# 05_LMS7002M_Misc.net
KiCad netlist of a schematic drawn in Altium Designer
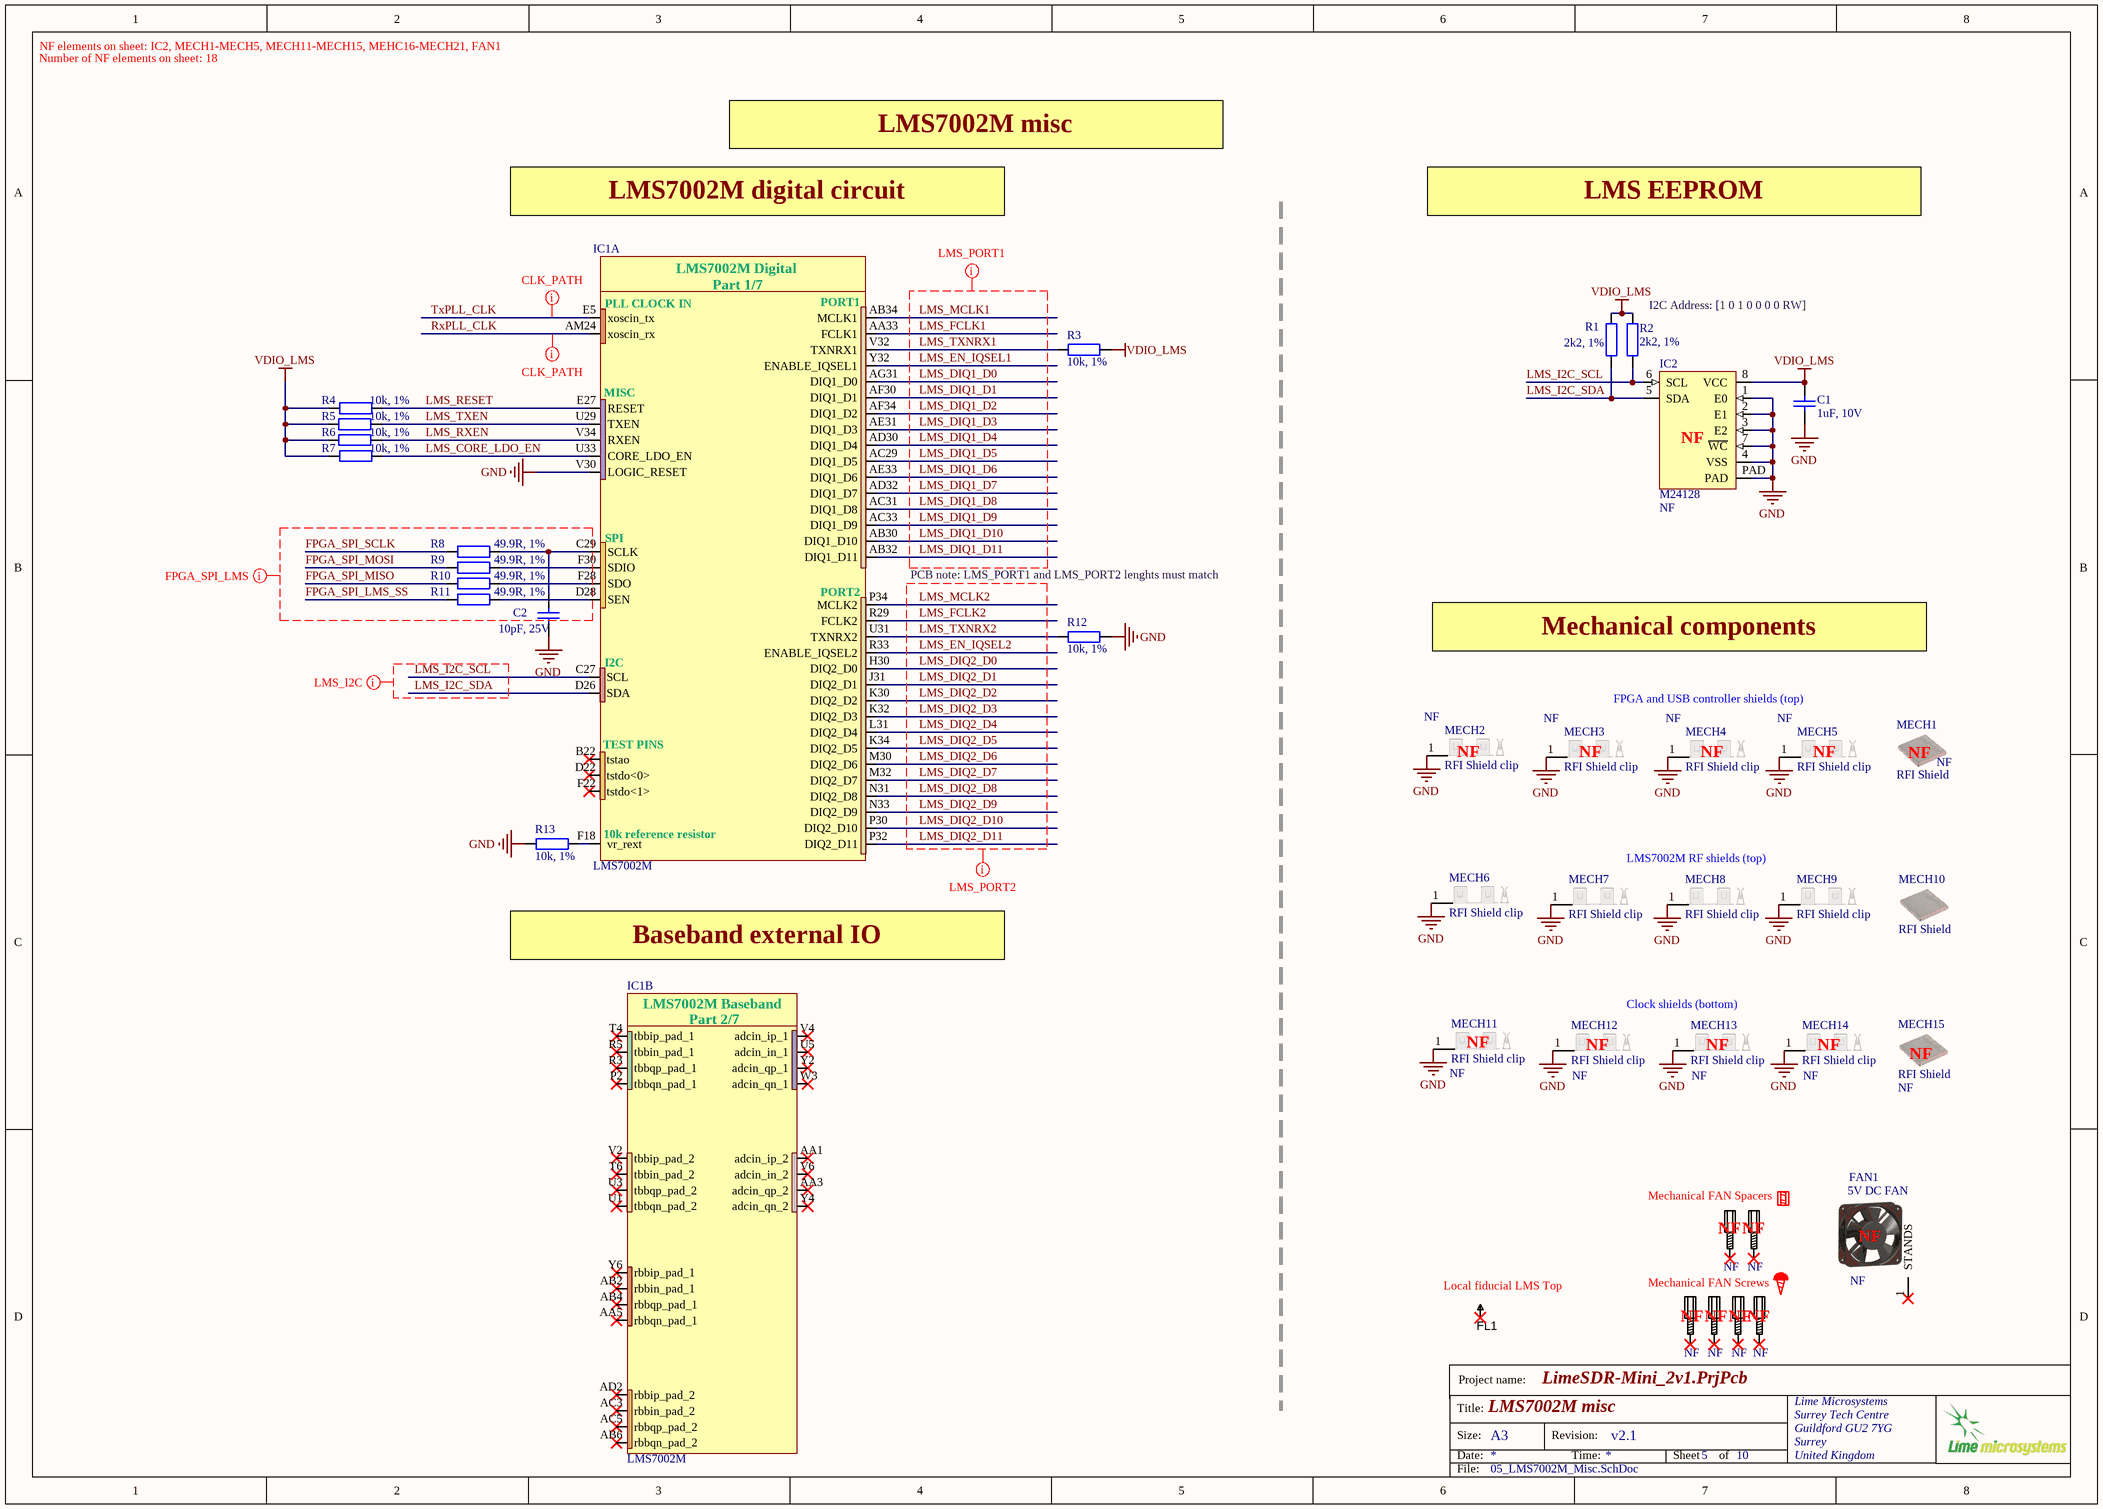
[diagram p0: 05_LMS7002M_Misc.SchDoc]

(export (version "E")
  (design (tool "Eeschema 10.0.6"))
  (components
    (comp (ref "C1")
      (value "1uF, 10V")
      (footprint "CAP0402")
      (fields (field (name "MANUFACTURER") "TDK"))
      (libsource (lib "LimeMicroAltiumLib_schLib") (part "Cap_0402"))
    )
    (comp (ref "C2")
      (value "10pF, 25V")
      (footprint "CAP0402")
      (fields (field (name "MANUFACTURER") "AVX"))
      (libsource (lib "LimeMicroAltiumLib_schLib") (part "Cap_0402"))
    )
    (comp (ref "FAN1")
      (value "5V DC FAN")
      (fields (field (name "MANUFACTURER") "Sunon Fans") (field (name "ASSEMBLY INFO") "NF"))
      (libsource (lib "LimeMicroAltiumLib_schLib") (part "12V_DC_FAN"))
    )
    (comp (ref "FL1")
      (value "Fiducial")
      (footprint "Fiducial_local")
      (libsource (lib "VGTU_Altium_lib") (part "Fiducial"))
    )
    (comp (ref "IC1")
      (value "LMS7002M")
      (footprint "LMS7002M_v5")
      (description "Schematic symbol revision 4. Default footprint - 0.31mm pad")
      (fields (field (name "MANUFACTURER") "Lime Microsystems"))
      (libsource (lib "LimeMicroAltiumLib_schLib_r04") (part "LMS7002Mr4"))
    )
    (comp (ref "IC2")
      (value "M24128")
      (footprint "M24128-DFMC6TG")
      (fields (field (name "MANUFACTURER") "STMicroelectronics") (field (name "ASSEMBLY INFO") "NF"))
      (libsource (lib "LimeMicroAltiumLib_schLib") (part "M24128-DFMC6TG"))
    )
    (comp (ref "MECH1")
      (value "RFI Shield")
      (footprint "WurthElectronic_RF_shield")
      (fields (field (name "MANUFACTURER") "WURTH ELEKTRONIK") (field (name "ASSEMBLY INFO") "NF"))
      (libsource (lib "LimeMicroAltiumLib_schLib") (part "RFI_SHIELD_1"))
    )
    (comp (ref "MECH2")
      (value "RFI Shield clip")
      (footprint "RFI_SHIELD_CLPS_MINI")
      (fields (field (name "MANUFACTURER") "HARWIN") (field (name "ASSEMBLY INFO") "NF"))
      (libsource (lib "LimeMicroAltiumLib_schLib") (part "RFI_SHIELD_CLIP"))
    )
    (comp (ref "MECH3")
      (value "RFI Shield clip")
      (footprint "RFI_SHIELD_CLPS_MINI")
      (fields (field (name "MANUFACTURER") "HARWIN") (field (name "ASSEMBLY INFO") "NF"))
      (libsource (lib "LimeMicroAltiumLib_schLib") (part "RFI_SHIELD_CLIP"))
    )
    (comp (ref "MECH4")
      (value "RFI Shield clip")
      (footprint "RFI_SHIELD_CLPS_MINI")
      (fields (field (name "MANUFACTURER") "HARWIN") (field (name "ASSEMBLY INFO") "NF"))
      (libsource (lib "LimeMicroAltiumLib_schLib") (part "RFI_SHIELD_CLIP"))
    )
    (comp (ref "MECH5")
      (value "RFI Shield clip")
      (footprint "RFI_SHIELD_CLPS_MINI")
      (fields (field (name "MANUFACTURER") "HARWIN") (field (name "ASSEMBLY INFO") "NF"))
      (libsource (lib "LimeMicroAltiumLib_schLib") (part "RFI_SHIELD_CLIP"))
    )
    (comp (ref "MECH6")
      (value "RFI Shield clip")
      (footprint "RFI_SHIELD_CLPS_MINI")
      (fields (field (name "MANUFACTURER") "HARWIN"))
      (libsource (lib "LimeMicroAltiumLib_schLib") (part "RFI_SHIELD_CLIP"))
    )
    (comp (ref "MECH7")
      (value "RFI Shield clip")
      (footprint "RFI_SHIELD_CLPS_MINI")
      (fields (field (name "MANUFACTURER") "HARWIN"))
      (libsource (lib "LimeMicroAltiumLib_schLib") (part "RFI_SHIELD_CLIP"))
    )
    (comp (ref "MECH8")
      (value "RFI Shield clip")
      (footprint "RFI_SHIELD_CLPS_MINI")
      (fields (field (name "MANUFACTURER") "HARWIN"))
      (libsource (lib "LimeMicroAltiumLib_schLib") (part "RFI_SHIELD_CLIP"))
    )
    (comp (ref "MECH9")
      (value "RFI Shield clip")
      (footprint "RFI_SHIELD_CLPS_MINI")
      (fields (field (name "MANUFACTURER") "HARWIN"))
      (libsource (lib "LimeMicroAltiumLib_schLib") (part "RFI_SHIELD_CLIP"))
    )
    (comp (ref "MECH10")
      (value "RFI Shield")
      (footprint "WurthElectronic_RF_shield")
      (fields (field (name "MANUFACTURER") "WURTH ELEKTRONIK"))
      (libsource (lib "LimeMicroAltiumLib_schLib") (part "RFI_SHIELD_1"))
    )
    (comp (ref "MECH11")
      (value "RFI Shield clip")
      (footprint "RFI_SHIELD_CLPS_MINI")
      (fields (field (name "MANUFACTURER") "HARWIN") (field (name "ASSEMBLY INFO") "NF"))
      (libsource (lib "LimeMicroAltiumLib_schLib") (part "RFI_SHIELD_CLIP"))
    )
    (comp (ref "MECH12")
      (value "RFI Shield clip")
      (footprint "RFI_SHIELD_CLPS_MINI")
      (fields (field (name "MANUFACTURER") "HARWIN") (field (name "ASSEMBLY INFO") "NF"))
      (libsource (lib "LimeMicroAltiumLib_schLib") (part "RFI_SHIELD_CLIP"))
    )
    (comp (ref "MECH13")
      (value "RFI Shield clip")
      (footprint "RFI_SHIELD_CLPS_MINI")
      (fields (field (name "MANUFACTURER") "HARWIN") (field (name "ASSEMBLY INFO") "NF"))
      (libsource (lib "LimeMicroAltiumLib_schLib") (part "RFI_SHIELD_CLIP"))
    )
    (comp (ref "MECH14")
      (value "RFI Shield clip")
      (footprint "RFI_SHIELD_CLPS_MINI")
      (fields (field (name "MANUFACTURER") "HARWIN") (field (name "ASSEMBLY INFO") "NF"))
      (libsource (lib "LimeMicroAltiumLib_schLib") (part "RFI_SHIELD_CLIP"))
    )
    (comp (ref "MECH15")
      (value "RFI Shield")
      (footprint "WurthElectronic_RF_shield")
      (fields (field (name "MANUFACTURER") "WURTH ELEKTRONIK") (field (name "ASSEMBLY INFO") "NF"))
      (libsource (lib "LimeMicroAltiumLib_schLib") (part "RFI_SHIELD_1"))
    )
    (comp (ref "MECH16")
      (value "Spacer M3")
      (description "STANDOFF M/F MET 5MM HEX 10MM L")
      (fields (field (name "MANUFACTURER") "BOSSARD") (field (name "ASSEMBLY INFO") "NF"))
      (libsource (lib "LimeMicroAltiumLib_schLib") (part "STANDOFF_M-F_THREADED_M3x8x10mm_HEX_5mm dia"))
    )
    (comp (ref "MECH17")
      (value "Spacer M3")
      (description "STANDOFF M/F MET 5MM HEX 10MM L")
      (fields (field (name "MANUFACTURER") "BOSSARD") (field (name "ASSEMBLY INFO") "NF"))
      (libsource (lib "LimeMicroAltiumLib_schLib") (part "STANDOFF_M-F_THREADED_M3x8x10mm_HEX_5mm dia"))
    )
    (comp (ref "MECH18")
      (value "Screws M3 v1")
      (description "STANDOFF M/F MET 5MM HEX 10MM L")
      (fields (field (name "MANUFACTURER") "KRAFTBERG") (field (name "ASSEMBLY INFO") "NF"))
      (libsource (lib "LimeMicroAltiumLib_schLib") (part "STANDOFF_M-F_THREADED_M3x8x10mm_HEX_5mm dia"))
    )
    (comp (ref "MECH19")
      (value "Screws M3 v1")
      (description "STANDOFF M/F MET 5MM HEX 10MM L")
      (fields (field (name "MANUFACTURER") "KRAFTBERG") (field (name "ASSEMBLY INFO") "NF"))
      (libsource (lib "LimeMicroAltiumLib_schLib") (part "STANDOFF_M-F_THREADED_M3x8x10mm_HEX_5mm dia"))
    )
    (comp (ref "MECH20")
      (value "Screws M3 v2")
      (description "STANDOFF M/F MET 5MM HEX 10MM L")
      (fields (field (name "MANUFACTURER") "KRAFTBERG") (field (name "ASSEMBLY INFO") "NF"))
      (libsource (lib "LimeMicroAltiumLib_schLib") (part "STANDOFF_M-F_THREADED_M3x8x10mm_HEX_5mm dia"))
    )
    (comp (ref "MECH21")
      (value "Screws M3 v2")
      (description "STANDOFF M/F MET 5MM HEX 10MM L")
      (fields (field (name "MANUFACTURER") "KRAFTBERG") (field (name "ASSEMBLY INFO") "NF"))
      (libsource (lib "LimeMicroAltiumLib_schLib") (part "STANDOFF_M-F_THREADED_M3x8x10mm_HEX_5mm dia"))
    )
    (comp (ref "R1")
      (value "2k2, 1%")
      (footprint "RES0402")
      (fields (field (name "MANUFACTURER") "Stackpole Electronics Inc") (field (name "TOLERANCE") "±1%"))
      (libsource (lib "LimeMicroAltiumLib_schLib") (part "Res_0402"))
    )
    (comp (ref "R2")
      (value "2k2, 1%")
      (footprint "RES0402")
      (fields (field (name "MANUFACTURER") "Stackpole Electronics Inc") (field (name "TOLERANCE") "±1%"))
      (libsource (lib "LimeMicroAltiumLib_schLib") (part "Res_0402"))
    )
    (comp (ref "R3")
      (value "10k, 1%")
      (footprint "RES0402")
      (fields (field (name "MANUFACTURER") "Yageo") (field (name "TOLERANCE") "±1%"))
      (libsource (lib "LimeMicroAltiumLib_schLib") (part "Res_0402"))
    )
    (comp (ref "R4")
      (value "10k, 1%")
      (footprint "RES0402")
      (fields (field (name "MANUFACTURER") "Yageo") (field (name "TOLERANCE") "±1%"))
      (libsource (lib "LimeMicroAltiumLib_schLib") (part "Res_0402"))
    )
    (comp (ref "R5")
      (value "10k, 1%")
      (footprint "RES0402")
      (fields (field (name "MANUFACTURER") "Yageo") (field (name "TOLERANCE") "±1%"))
      (libsource (lib "LimeMicroAltiumLib_schLib") (part "Res_0402"))
    )
    (comp (ref "R6")
      (value "10k, 1%")
      (footprint "RES0402")
      (fields (field (name "MANUFACTURER") "Yageo") (field (name "TOLERANCE") "±1%"))
      (libsource (lib "LimeMicroAltiumLib_schLib") (part "Res_0402"))
    )
    (comp (ref "R7")
      (value "10k, 1%")
      (footprint "RES0402")
      (fields (field (name "MANUFACTURER") "Yageo") (field (name "TOLERANCE") "±1%"))
      (libsource (lib "LimeMicroAltiumLib_schLib") (part "Res_0402"))
    )
    (comp (ref "R8")
      (value "49.9R, 1%")
      (footprint "RES0402")
      (fields
        (field (name "TOLERANCE") "±1%")
        (field (name "MANUFACTURER") "Samsung Electro-Mechanics America, Inc.")
      )
      (libsource (lib "LimeMicroAltiumLib_schLib") (part "Res_0402"))
    )
    (comp (ref "R9")
      (value "49.9R, 1%")
      (footprint "RES0402")
      (fields
        (field (name "TOLERANCE") "±1%")
        (field (name "MANUFACTURER") "Samsung Electro-Mechanics America, Inc.")
      )
      (libsource (lib "LimeMicroAltiumLib_schLib") (part "Res_0402"))
    )
    (comp (ref "R10")
      (value "49.9R, 1%")
      (footprint "RES0402")
      (fields
        (field (name "TOLERANCE") "±1%")
        (field (name "MANUFACTURER") "Samsung Electro-Mechanics America, Inc.")
      )
      (libsource (lib "LimeMicroAltiumLib_schLib") (part "Res_0402"))
    )
    (comp (ref "R11")
      (value "49.9R, 1%")
      (footprint "RES0402")
      (fields
        (field (name "TOLERANCE") "±1%")
        (field (name "MANUFACTURER") "Samsung Electro-Mechanics America, Inc.")
      )
      (libsource (lib "LimeMicroAltiumLib_schLib") (part "Res_0402"))
    )
    (comp (ref "R12")
      (value "10k, 1%")
      (footprint "RES0402")
      (fields (field (name "MANUFACTURER") "Yageo") (field (name "TOLERANCE") "±1%"))
      (libsource (lib "LimeMicroAltiumLib_schLib") (part "Res_0402"))
    )
    (comp (ref "R13")
      (value "10k, 1%")
      (footprint "RES0402")
      (fields (field (name "MANUFACTURER") "Yageo") (field (name "TOLERANCE") "±1%"))
      (libsource (lib "LimeMicroAltiumLib_schLib") (part "Res_0402"))
    )
  )
  (nets
    (net (code "1") (name "/FPGA_SPI_LMS_SS") (class "Default")
      (node (ref "R11") (pin "2") (pinfunction "2_2") (pintype "passive"))
    )
    (net (code "2") (name "/FPGA_SPI_MISO") (class "Default")
      (node (ref "R10") (pin "2") (pinfunction "2_2") (pintype "passive"))
    )
    (net (code "3") (name "/FPGA_SPI_MOSI") (class "Default")
      (node (ref "R9") (pin "2") (pinfunction "2_2") (pintype "passive"))
    )
    (net (code "4") (name "/FPGA_SPI_SCLK") (class "Default")
      (node (ref "R8") (pin "2") (pinfunction "2_2") (pintype "passive"))
    )
    (net (code "5") (name "/LMS_CORE_LDO_EN") (class "Default")
      (node (ref "IC1") (pin "U33") (pinfunction "CORE_LDO_EN_U33") (pintype "passive"))
      (node (ref "R7") (pin "1") (pinfunction "1_1") (pintype "passive"))
    )
    (net (code "6") (name "/LMS_DIQ1_D0") (class "Default")
      (node (ref "IC1") (pin "AG31") (pinfunction "DIQ1_D0_AG31") (pintype "passive"))
    )
    (net (code "7") (name "/LMS_DIQ1_D1") (class "Default")
      (node (ref "IC1") (pin "AF30") (pinfunction "DIQ1_D1_AF30") (pintype "passive"))
    )
    (net (code "8") (name "/LMS_DIQ1_D2") (class "Default")
      (node (ref "IC1") (pin "AF34") (pinfunction "DIQ1_D2_AF34") (pintype "passive"))
    )
    (net (code "9") (name "/LMS_DIQ1_D3") (class "Default")
      (node (ref "IC1") (pin "AE31") (pinfunction "DIQ1_D3_AE31") (pintype "passive"))
    )
    (net (code "10") (name "/LMS_DIQ1_D4") (class "Default")
      (node (ref "IC1") (pin "AD30") (pinfunction "DIQ1_D4_AD30") (pintype "passive"))
    )
    (net (code "11") (name "/LMS_DIQ1_D5") (class "Default")
      (node (ref "IC1") (pin "AC29") (pinfunction "DIQ1_D5_AC29") (pintype "passive"))
    )
    (net (code "12") (name "/LMS_DIQ1_D6") (class "Default")
      (node (ref "IC1") (pin "AE33") (pinfunction "DIQ1_D6_AE33") (pintype "passive"))
    )
    (net (code "13") (name "/LMS_DIQ1_D7") (class "Default")
      (node (ref "IC1") (pin "AD32") (pinfunction "DIQ1_D7_AD32") (pintype "passive"))
    )
    (net (code "14") (name "/LMS_DIQ1_D8") (class "Default")
      (node (ref "IC1") (pin "AC31") (pinfunction "DIQ1_D8_AC31") (pintype "passive"))
    )
    (net (code "15") (name "/LMS_DIQ1_D9") (class "Default")
      (node (ref "IC1") (pin "AC33") (pinfunction "DIQ1_D9_AC33") (pintype "passive"))
    )
    (net (code "16") (name "/LMS_DIQ1_D10") (class "Default")
      (node (ref "IC1") (pin "AB30") (pinfunction "DIQ1_D10_AB30") (pintype "passive"))
    )
    (net (code "17") (name "/LMS_DIQ1_D11") (class "Default")
      (node (ref "IC1") (pin "AB32") (pinfunction "DIQ1_D11_AB32") (pintype "passive"))
    )
    (net (code "18") (name "/LMS_DIQ2_D0") (class "Default")
      (node (ref "IC1") (pin "H30") (pinfunction "DIQ2_D0_H30") (pintype "passive"))
    )
    (net (code "19") (name "/LMS_DIQ2_D1") (class "Default")
      (node (ref "IC1") (pin "J31") (pinfunction "DIQ2_D1_J31") (pintype "passive"))
    )
    (net (code "20") (name "/LMS_DIQ2_D2") (class "Default")
      (node (ref "IC1") (pin "K30") (pinfunction "DIQ2_D2_K30") (pintype "passive"))
    )
    (net (code "21") (name "/LMS_DIQ2_D3") (class "Default")
      (node (ref "IC1") (pin "K32") (pinfunction "DIQ2_D3_K32") (pintype "passive"))
    )
    (net (code "22") (name "/LMS_DIQ2_D4") (class "Default")
      (node (ref "IC1") (pin "L31") (pinfunction "DIQ2_D4_L31") (pintype "passive"))
    )
    (net (code "23") (name "/LMS_DIQ2_D5") (class "Default")
      (node (ref "IC1") (pin "K34") (pinfunction "DIQ2_D5_K34") (pintype "passive"))
    )
    (net (code "24") (name "/LMS_DIQ2_D6") (class "Default")
      (node (ref "IC1") (pin "M30") (pinfunction "DIQ2_D6_M30") (pintype "passive"))
    )
    (net (code "25") (name "/LMS_DIQ2_D7") (class "Default")
      (node (ref "IC1") (pin "M32") (pinfunction "DIQ2_D7_M32") (pintype "passive"))
    )
    (net (code "26") (name "/LMS_DIQ2_D8") (class "Default")
      (node (ref "IC1") (pin "N31") (pinfunction "DIQ2_D8_N31") (pintype "passive"))
    )
    (net (code "27") (name "/LMS_DIQ2_D9") (class "Default")
      (node (ref "IC1") (pin "N33") (pinfunction "DIQ2_D9_N33") (pintype "passive"))
    )
    (net (code "28") (name "/LMS_DIQ2_D10") (class "Default")
      (node (ref "IC1") (pin "P30") (pinfunction "DIQ2_D10_P30") (pintype "passive"))
    )
    (net (code "29") (name "/LMS_DIQ2_D11") (class "Default")
      (node (ref "IC1") (pin "P32") (pinfunction "DIQ2_D11_P32") (pintype "passive"))
    )
    (net (code "30") (name "/LMS_EN_IQSEL1") (class "Default")
      (node (ref "IC1") (pin "Y32") (pinfunction "ENABLE_IQSEL1_Y32") (pintype "passive"))
    )
    (net (code "31") (name "/LMS_EN_IQSEL2") (class "Default")
      (node (ref "IC1") (pin "R33") (pinfunction "ENABLE_IQSEL2_R33") (pintype "passive"))
    )
    (net (code "32") (name "/LMS_FCLK1") (class "Default")
      (node (ref "IC1") (pin "AA33") (pinfunction "FCLK1_AA33") (pintype "passive"))
    )
    (net (code "33") (name "/LMS_FCLK2") (class "Default")
      (node (ref "IC1") (pin "R29") (pinfunction "FCLK2_R29") (pintype "passive"))
    )
    (net (code "34") (name "/LMS_I2C_SCL") (class "Default")
      (node (ref "IC1") (pin "C27") (pinfunction "SCL_C27") (pintype "passive"))
      (node (ref "IC2") (pin "6") (pinfunction "SCL_6") (pintype "input"))
      (node (ref "R2") (pin "2") (pinfunction "2_2") (pintype "passive"))
    )
    (net (code "35") (name "/LMS_I2C_SDA") (class "Default")
      (node (ref "IC1") (pin "D26") (pinfunction "SDA_D26") (pintype "passive"))
      (node (ref "IC2") (pin "5") (pinfunction "SDA_5") (pintype "bidirectional"))
      (node (ref "R1") (pin "2") (pinfunction "2_2") (pintype "passive"))
    )
    (net (code "36") (name "/LMS_MCLK1") (class "Default")
      (node (ref "IC1") (pin "AB34") (pinfunction "MCLK1_AB34") (pintype "passive"))
    )
    (net (code "37") (name "/LMS_MCLK2") (class "Default")
      (node (ref "IC1") (pin "P34") (pinfunction "MCLK2_P34") (pintype "passive"))
    )
    (net (code "38") (name "/LMS_RESET") (class "Default")
      (node (ref "IC1") (pin "E27") (pinfunction "RESET_E27") (pintype "passive"))
      (node (ref "R4") (pin "1") (pinfunction "1_1") (pintype "passive"))
    )
    (net (code "39") (name "/LMS_RXEN") (class "Default")
      (node (ref "IC1") (pin "V34") (pinfunction "RXEN_V34") (pintype "passive"))
      (node (ref "R6") (pin "2") (pinfunction "2_2") (pintype "passive"))
    )
    (net (code "40") (name "/LMS_TXEN") (class "Default")
      (node (ref "IC1") (pin "U29") (pinfunction "TXEN_U29") (pintype "passive"))
      (node (ref "R5") (pin "2") (pinfunction "2_2") (pintype "passive"))
    )
    (net (code "41") (name "/LMS_TXNRX1") (class "Default")
      (node (ref "IC1") (pin "V32") (pinfunction "TXNRX1_V32") (pintype "passive"))
      (node (ref "R3") (pin "1") (pinfunction "1_1") (pintype "passive"))
    )
    (net (code "42") (name "/LMS_TXNRX2") (class "Default")
      (node (ref "IC1") (pin "U31") (pinfunction "TXNRX2_U31") (pintype "passive"))
      (node (ref "R12") (pin "1") (pinfunction "1_1") (pintype "passive"))
    )
    (net (code "43") (name "/RxPLL_CLK") (class "Default")
      (node (ref "IC1") (pin "AM24") (pinfunction "xoscin_rx_AM24") (pintype "passive"))
    )
    (net (code "44") (name "/TxPLL_CLK") (class "Default")
      (node (ref "IC1") (pin "E5") (pinfunction "xoscin_tx_E5") (pintype "passive"))
    )
    (net (code "45") (name "GND") (class "Default")
      (node (ref "C1") (pin "2") (pinfunction "2_2") (pintype "passive"))
      (node (ref "C2") (pin "2") (pinfunction "2_2") (pintype "passive"))
      (node (ref "IC1") (pin "V30") (pinfunction "LOGIC_RESET_V30") (pintype "passive"))
      (node (ref "IC2") (pin "1") (pinfunction "E0_1") (pintype "input"))
      (node (ref "IC2") (pin "2") (pinfunction "E1_2") (pintype "input"))
      (node (ref "IC2") (pin "3") (pinfunction "E2_3") (pintype "input"))
      (node (ref "IC2") (pin "4") (pinfunction "VSS_4") (pintype "power_in"))
      (node (ref "IC2") (pin "7") (pinfunction "~{WC}_7") (pintype "input"))
      (node (ref "IC2") (pin "PAD") (pinfunction "PAD_PAD") (pintype "power_in"))
      (node (ref "MECH11") (pin "1") (pinfunction "GND_1") (pintype "passive"))
      (node (ref "MECH12") (pin "1") (pinfunction "GND_1") (pintype "passive"))
      (node (ref "MECH13") (pin "1") (pinfunction "GND_1") (pintype "passive"))
      (node (ref "MECH14") (pin "1") (pinfunction "GND_1") (pintype "passive"))
      (node (ref "MECH2") (pin "1") (pinfunction "GND_1") (pintype "passive"))
      (node (ref "MECH3") (pin "1") (pinfunction "GND_1") (pintype "passive"))
      (node (ref "MECH4") (pin "1") (pinfunction "GND_1") (pintype "passive"))
      (node (ref "MECH5") (pin "1") (pinfunction "GND_1") (pintype "passive"))
      (node (ref "MECH6") (pin "1") (pinfunction "GND_1") (pintype "passive"))
      (node (ref "MECH7") (pin "1") (pinfunction "GND_1") (pintype "passive"))
      (node (ref "MECH8") (pin "1") (pinfunction "GND_1") (pintype "passive"))
      (node (ref "MECH9") (pin "1") (pinfunction "GND_1") (pintype "passive"))
      (node (ref "R12") (pin "2") (pinfunction "2_2") (pintype "passive"))
      (node (ref "R13") (pin "2") (pinfunction "2_2") (pintype "passive"))
    )
    (net (code "46") (name "Net-(IC1A-SCLK)") (class "Default")
      (node (ref "C2") (pin "1") (pinfunction "1_1") (pintype "passive"))
      (node (ref "IC1") (pin "C29") (pinfunction "SCLK_C29") (pintype "passive"))
      (node (ref "R8") (pin "1") (pinfunction "1_1") (pintype "passive"))
    )
    (net (code "47") (name "Net-(IC1A-SDIO)") (class "Default")
      (node (ref "IC1") (pin "F30") (pinfunction "SDIO_F30") (pintype "passive"))
      (node (ref "R9") (pin "1") (pinfunction "1_1") (pintype "passive"))
    )
    (net (code "48") (name "Net-(IC1A-SDO)") (class "Default")
      (node (ref "IC1") (pin "F28") (pinfunction "SDO_F28") (pintype "passive"))
      (node (ref "R10") (pin "1") (pinfunction "1_1") (pintype "passive"))
    )
    (net (code "49") (name "Net-(IC1A-SEN)") (class "Default")
      (node (ref "IC1") (pin "D28") (pinfunction "SEN_D28") (pintype "passive"))
      (node (ref "R11") (pin "1") (pinfunction "1_1") (pintype "passive"))
    )
    (net (code "50") (name "Net-(IC1A-vr_rext)") (class "Default")
      (node (ref "IC1") (pin "F18") (pinfunction "vr_rext_F18") (pintype "passive"))
      (node (ref "R13") (pin "1") (pinfunction "1_1") (pintype "passive"))
    )
    (net (code "51") (name "VDIO_LMS") (class "Default")
      (node (ref "C1") (pin "1") (pinfunction "1_1") (pintype "passive"))
      (node (ref "IC2") (pin "8") (pinfunction "VCC_8") (pintype "power_in"))
      (node (ref "R1") (pin "1") (pinfunction "1_1") (pintype "passive"))
      (node (ref "R2") (pin "1") (pinfunction "1_1") (pintype "passive"))
      (node (ref "R3") (pin "2") (pinfunction "2_2") (pintype "passive"))
      (node (ref "R4") (pin "2") (pinfunction "2_2") (pintype "passive"))
      (node (ref "R5") (pin "1") (pinfunction "1_1") (pintype "passive"))
      (node (ref "R6") (pin "1") (pinfunction "1_1") (pintype "passive"))
      (node (ref "R7") (pin "2") (pinfunction "2_2") (pintype "passive"))
    )
    (net (code "52") (name "unconnected-(FAN1-STANDS-Pad1)") (class "Default")
      (node (ref "FAN1") (pin "1") (pinfunction "STANDS_1") (pintype "passive+no_connect"))
    )
    (net (code "53") (name "unconnected-(FL1-Pad1)") (class "Default")
      (node (ref "FL1") (pin "1") (pintype "passive+no_connect"))
    )
    (net (code "54") (name "unconnected-(IC1A-tstao-PadB22)") (class "Default")
      (node (ref "IC1") (pin "B22") (pinfunction "tstao_B22") (pintype "passive+no_connect"))
    )
    (net (code "55") (name "unconnected-(IC1A-tstdo<0>-PadD22)") (class "Default")
      (node (ref "IC1") (pin "D22") (pinfunction "tstdo<0>_D22") (pintype "passive+no_connect"))
    )
    (net (code "56") (name "unconnected-(IC1A-tstdo<1>-PadF22)") (class "Default")
      (node (ref "IC1") (pin "F22") (pinfunction "tstdo<1>_F22") (pintype "passive+no_connect"))
    )
    (net (code "57") (name "unconnected-(IC1B-adcin_in_1-PadU5)") (class "Default")
      (node (ref "IC1") (pin "U5") (pinfunction "adcin_in_1_U5") (pintype "passive+no_connect"))
    )
    (net (code "58") (name "unconnected-(IC1B-adcin_in_2-PadV6)") (class "Default")
      (node (ref "IC1") (pin "V6") (pinfunction "adcin_in_2_V6") (pintype "passive+no_connect"))
    )
    (net (code "59") (name "unconnected-(IC1B-adcin_ip_1-PadV4)") (class "Default")
      (node (ref "IC1") (pin "V4") (pinfunction "adcin_ip_1_V4") (pintype "passive+no_connect"))
    )
    (net (code "60") (name "unconnected-(IC1B-adcin_ip_2-PadAA1)") (class "Default")
      (node (ref "IC1") (pin "AA1") (pinfunction "adcin_ip_2_AA1") (pintype "passive+no_connect"))
    )
    (net (code "61") (name "unconnected-(IC1B-adcin_qn_1-PadW3)") (class "Default")
      (node (ref "IC1") (pin "W3") (pinfunction "adcin_qn_1_W3") (pintype "passive+no_connect"))
    )
    (net (code "62") (name "unconnected-(IC1B-adcin_qn_2-PadY4)") (class "Default")
      (node (ref "IC1") (pin "Y4") (pinfunction "adcin_qn_2_Y4") (pintype "passive+no_connect"))
    )
    (net (code "63") (name "unconnected-(IC1B-adcin_qp_1-PadY2)") (class "Default")
      (node (ref "IC1") (pin "Y2") (pinfunction "adcin_qp_1_Y2") (pintype "passive+no_connect"))
    )
    (net (code "64") (name "unconnected-(IC1B-adcin_qp_2-PadAA3)") (class "Default")
      (node (ref "IC1") (pin "AA3") (pinfunction "adcin_qp_2_AA3") (pintype "passive+no_connect"))
    )
    (net (code "65") (name "unconnected-(IC1B-rbbin_pad_1-PadAB2)") (class "Default")
      (node (ref "IC1") (pin "AB2") (pinfunction "rbbin_pad_1_AB2") (pintype "passive+no_connect"))
    )
    (net (code "66") (name "unconnected-(IC1B-rbbin_pad_2-PadAC3)") (class "Default")
      (node (ref "IC1") (pin "AC3") (pinfunction "rbbin_pad_2_AC3") (pintype "passive+no_connect"))
    )
    (net (code "67") (name "unconnected-(IC1B-rbbip_pad_1-PadY6)") (class "Default")
      (node (ref "IC1") (pin "Y6") (pinfunction "rbbip_pad_1_Y6") (pintype "passive+no_connect"))
    )
    (net (code "68") (name "unconnected-(IC1B-rbbip_pad_2-PadAD2)") (class "Default")
      (node (ref "IC1") (pin "AD2") (pinfunction "rbbip_pad_2_AD2") (pintype "passive+no_connect"))
    )
    (net (code "69") (name "unconnected-(IC1B-rbbqn_pad_1-PadAA5)") (class "Default")
      (node (ref "IC1") (pin "AA5") (pinfunction "rbbqn_pad_1_AA5") (pintype "passive+no_connect"))
    )
    (net (code "70") (name "unconnected-(IC1B-rbbqn_pad_2-PadAB6)") (class "Default")
      (node (ref "IC1") (pin "AB6") (pinfunction "rbbqn_pad_2_AB6") (pintype "passive+no_connect"))
    )
    (net (code "71") (name "unconnected-(IC1B-rbbqp_pad_1-PadAB4)") (class "Default")
      (node (ref "IC1") (pin "AB4") (pinfunction "rbbqp_pad_1_AB4") (pintype "passive+no_connect"))
    )
    (net (code "72") (name "unconnected-(IC1B-rbbqp_pad_2-PadAC5)") (class "Default")
      (node (ref "IC1") (pin "AC5") (pinfunction "rbbqp_pad_2_AC5") (pintype "passive+no_connect"))
    )
    (net (code "73") (name "unconnected-(IC1B-tbbin_pad_1-PadR5)") (class "Default")
      (node (ref "IC1") (pin "R5") (pinfunction "tbbin_pad_1_R5") (pintype "passive+no_connect"))
    )
    (net (code "74") (name "unconnected-(IC1B-tbbin_pad_2-PadT6)") (class "Default")
      (node (ref "IC1") (pin "T6") (pinfunction "tbbin_pad_2_T6") (pintype "passive+no_connect"))
    )
    (net (code "75") (name "unconnected-(IC1B-tbbip_pad_1-PadT4)") (class "Default")
      (node (ref "IC1") (pin "T4") (pinfunction "tbbip_pad_1_T4") (pintype "passive+no_connect"))
    )
    (net (code "76") (name "unconnected-(IC1B-tbbip_pad_2-PadV2)") (class "Default")
      (node (ref "IC1") (pin "V2") (pinfunction "tbbip_pad_2_V2") (pintype "passive+no_connect"))
    )
    (net (code "77") (name "unconnected-(IC1B-tbbqn_pad_1-PadP2)") (class "Default")
      (node (ref "IC1") (pin "P2") (pinfunction "tbbqn_pad_1_P2") (pintype "passive+no_connect"))
    )
    (net (code "78") (name "unconnected-(IC1B-tbbqn_pad_2-PadU1)") (class "Default")
      (node (ref "IC1") (pin "U1") (pinfunction "tbbqn_pad_2_U1") (pintype "passive+no_connect"))
    )
    (net (code "79") (name "unconnected-(IC1B-tbbqp_pad_1-PadR3)") (class "Default")
      (node (ref "IC1") (pin "R3") (pinfunction "tbbqp_pad_1_R3") (pintype "passive+no_connect"))
    )
    (net (code "80") (name "unconnected-(IC1B-tbbqp_pad_2-PadU3)") (class "Default")
      (node (ref "IC1") (pin "U3") (pinfunction "tbbqp_pad_2_U3") (pintype "passive+no_connect"))
    )
    (net (code "81") (name "unconnected-(MECH16-PadMH1)") (class "Default")
      (node (ref "MECH16") (pin "MH1") (pinfunction "MH1_MH1") (pintype "passive+no_connect"))
    )
    (net (code "82") (name "unconnected-(MECH17-PadMH1)") (class "Default")
      (node (ref "MECH17") (pin "MH1") (pinfunction "MH1_MH1") (pintype "passive+no_connect"))
    )
    (net (code "83") (name "unconnected-(MECH18-PadMH1)") (class "Default")
      (node (ref "MECH18") (pin "MH1") (pinfunction "MH1_MH1") (pintype "passive+no_connect"))
    )
    (net (code "84") (name "unconnected-(MECH19-PadMH1)") (class "Default")
      (node (ref "MECH19") (pin "MH1") (pinfunction "MH1_MH1") (pintype "passive+no_connect"))
    )
    (net (code "85") (name "unconnected-(MECH20-PadMH1)") (class "Default")
      (node (ref "MECH20") (pin "MH1") (pinfunction "MH1_MH1") (pintype "passive+no_connect"))
    )
    (net (code "86") (name "unconnected-(MECH21-PadMH1)") (class "Default")
      (node (ref "MECH21") (pin "MH1") (pinfunction "MH1_MH1") (pintype "passive+no_connect"))
    )
  )
)
